# I2CSlave_OnBoard.net
KiCad netlist of a schematic drawn in EAGLE
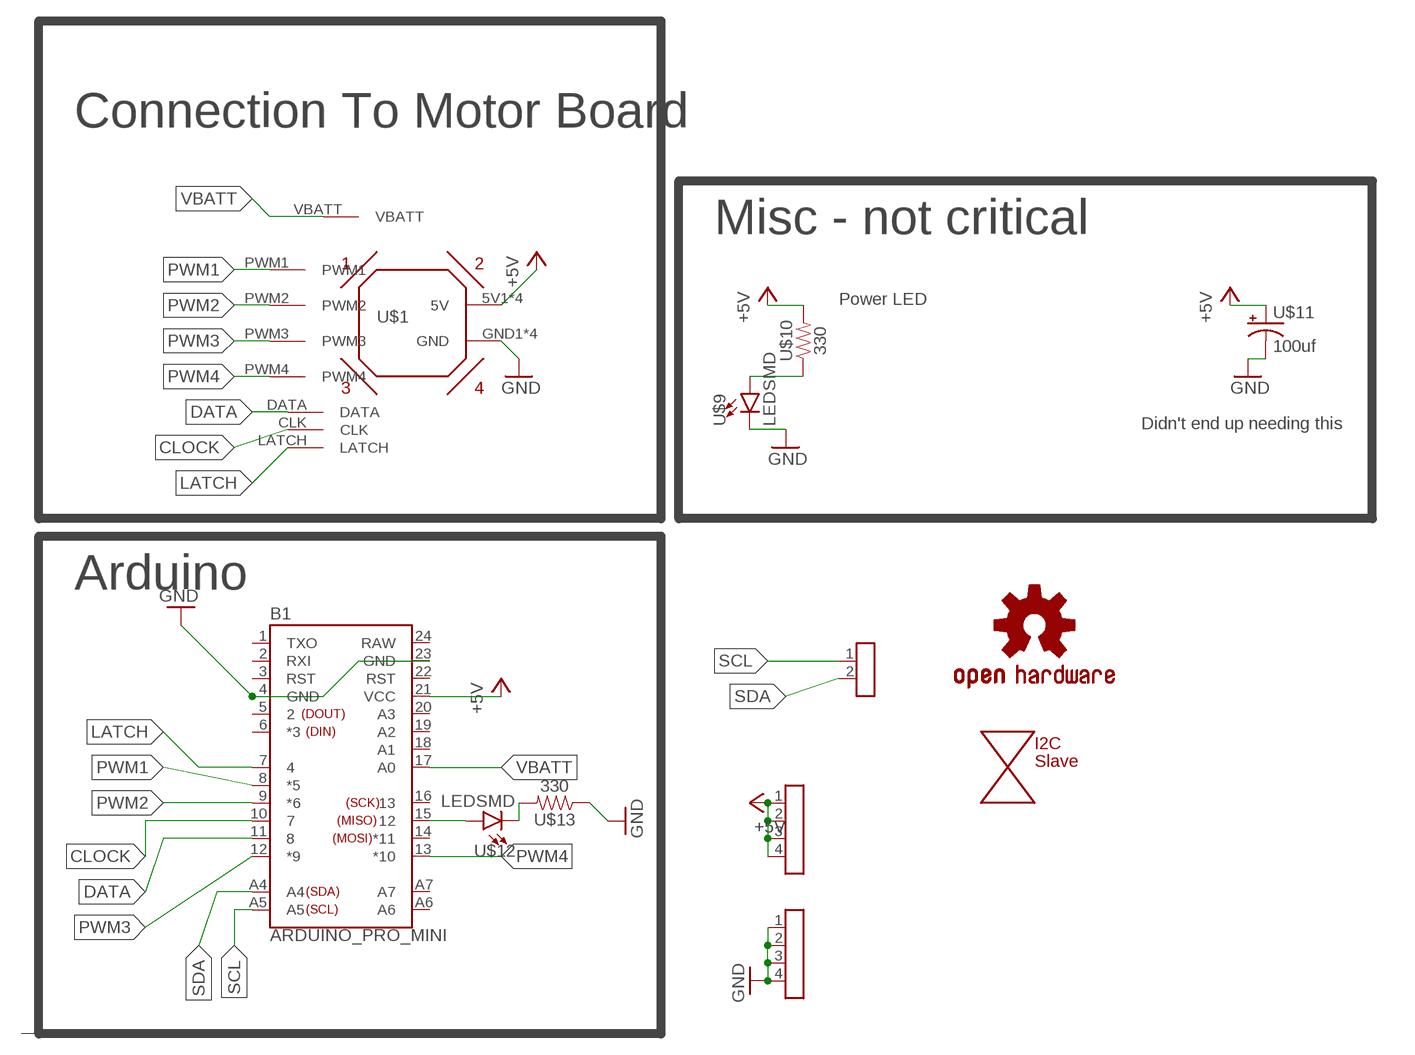
[diagram p0: schematic, sheet 1]

(export (version "E")
  (design (tool "Eeschema 10.0.6"))
  (components
    (comp (ref "B1")
      (value "ARDUINO_PRO_MINI")
      (footprint "eagle-import:ARDUINO_PRO_MINI")
      (libsource (lib "eagle-import") (part "ARDUINO_PRO_MINI"))
    )
    (comp (ref "I2C")
      (value "Slave")
      (footprint "eagle-import:ANNOTATION")
      (libsource (lib "eagle-import") (part "ANNOTATION"))
    )
    (comp (ref "LOGO1")
      (value "OSHW-LOGOM")
      (footprint "eagle-import:OSHW-LOGO-M")
      (libsource (lib "eagle-import") (part "OSHW-LOGOM"))
    )
    (comp (ref "U$1")
      (value "OMNIBOARD")
      (footprint "eagle-import:OMNIBOARD")
      (libsource (lib "eagle-import") (part "OMNIBOARD"))
    )
    (comp (ref "U$2")
      (value "2XHEADER")
      (footprint "eagle-import:2XHEADER")
      (libsource (lib "eagle-import") (part "2XHEADER"))
    )
    (comp (ref "U$3")
      (value "4XHEADER")
      (footprint "eagle-import:4XHEADER")
      (libsource (lib "eagle-import") (part "4XHEADER"))
    )
    (comp (ref "U$4")
      (value "4XHEADER")
      (footprint "eagle-import:4XHEADER")
      (libsource (lib "eagle-import") (part "4XHEADER"))
    )
    (comp (ref "U$9")
      (value "LEDSMD")
      (footprint "eagle-import:LED_SMD")
      (libsource (lib "eagle-import") (part "LEDSMD"))
    )
    (comp (ref "U$10")
      (value "330")
      (footprint "eagle-import:R1206")
      (libsource (lib "eagle-import") (part "RESISTORSMD"))
    )
    (comp (ref "U$11")
      (value "100uf")
      (footprint "eagle-import:CAP_E")
      (libsource (lib "eagle-import") (part "CAP_EMED"))
    )
    (comp (ref "U$12")
      (value "LEDSMD")
      (footprint "eagle-import:LED_SMD")
      (libsource (lib "eagle-import") (part "LEDSMD"))
    )
    (comp (ref "U$13")
      (value "330")
      (footprint "eagle-import:R1206")
      (libsource (lib "eagle-import") (part "RESISTORSMD"))
    )
  )
  (nets
    (net (code "1") (name "+5V") (class "Default")
      (node (ref "B1") (pin "21") (pinfunction "VCC_21") (pintype "power_in"))
      (node (ref "U$1") (pin "5V1") (pinfunction "5V_5V1") (pintype "passive"))
      (node (ref "U$1") (pin "5V2") (pinfunction "5V_5V2") (pintype "passive"))
      (node (ref "U$1") (pin "5V3") (pinfunction "5V_5V3") (pintype "passive"))
      (node (ref "U$1") (pin "5V4") (pinfunction "5V_5V4") (pintype "passive"))
      (node (ref "U$10") (pin "2") (pinfunction "2_2") (pintype "passive"))
      (node (ref "U$11") (pin "+") (pinfunction "+_+") (pintype "passive"))
      (node (ref "U$3") (pin "1") (pinfunction "1_1") (pintype "passive"))
      (node (ref "U$3") (pin "2") (pinfunction "2_2") (pintype "passive"))
      (node (ref "U$3") (pin "3") (pinfunction "3_3") (pintype "passive"))
      (node (ref "U$3") (pin "4") (pinfunction "4_4") (pintype "passive"))
    )
    (net (code "2") (name "/RAW") (class "Default")
      (node (ref "B1") (pin "24") (pinfunction "RAW_24") (pintype "power_in"))
    )
    (net (code "3") (name "CLOCK") (class "Default")
      (node (ref "B1") (pin "10") (pinfunction "7_10") (pintype "bidirectional"))
      (node (ref "U$1") (pin "CLK") (pinfunction "CLK_CLK") (pintype "passive"))
    )
    (net (code "4") (name "DATA") (class "Default")
      (node (ref "B1") (pin "11") (pinfunction "8_11") (pintype "bidirectional"))
      (node (ref "U$1") (pin "DATA") (pinfunction "DATA_DATA") (pintype "passive"))
    )
    (net (code "5") (name "GND") (class "Default")
      (node (ref "B1") (pin "23") (pinfunction "GND_23") (pintype "power_in"))
      (node (ref "B1") (pin "4") (pinfunction "GND_4") (pintype "power_in"))
      (node (ref "U$1") (pin "GND1") (pinfunction "GND_GND1") (pintype "passive"))
      (node (ref "U$1") (pin "GND2") (pinfunction "GND_GND2") (pintype "passive"))
      (node (ref "U$1") (pin "GND3") (pinfunction "GND_GND3") (pintype "passive"))
      (node (ref "U$1") (pin "GND4") (pinfunction "GND_GND4") (pintype "passive"))
      (node (ref "U$11") (pin "-") (pinfunction "-_-") (pintype "passive"))
      (node (ref "U$13") (pin "1") (pinfunction "1_1") (pintype "passive"))
      (node (ref "U$4") (pin "1") (pinfunction "1_1") (pintype "passive"))
      (node (ref "U$4") (pin "2") (pinfunction "2_2") (pintype "passive"))
      (node (ref "U$4") (pin "3") (pinfunction "3_3") (pintype "passive"))
      (node (ref "U$4") (pin "4") (pinfunction "4_4") (pintype "passive"))
      (node (ref "U$9") (pin "C") (pinfunction "C_C") (pintype "passive"))
    )
    (net (code "6") (name "LATCH") (class "Default")
      (node (ref "B1") (pin "7") (pinfunction "4_7") (pintype "bidirectional"))
      (node (ref "U$1") (pin "LATCH") (pinfunction "LATCH_LATCH") (pintype "passive"))
    )
    (net (code "7") (name "Net-(B1-12)") (class "Default")
      (node (ref "B1") (pin "15") (pinfunction "12_15") (pintype "bidirectional"))
      (node (ref "U$12") (pin "A") (pinfunction "A_A") (pintype "passive"))
    )
    (net (code "8") (name "Net-(U$10-Pad1)") (class "Default")
      (node (ref "U$10") (pin "1") (pinfunction "1_1") (pintype "passive"))
      (node (ref "U$9") (pin "A") (pinfunction "A_A") (pintype "passive"))
    )
    (net (code "9") (name "Net-(U$12-PadC)") (class "Default")
      (node (ref "U$12") (pin "C") (pinfunction "C_C") (pintype "passive"))
      (node (ref "U$13") (pin "2") (pinfunction "2_2") (pintype "passive"))
    )
    (net (code "10") (name "PWM1") (class "Default")
      (node (ref "B1") (pin "8") (pinfunction "*5_8") (pintype "bidirectional"))
      (node (ref "U$1") (pin "PWM1") (pinfunction "PWM1_PWM1") (pintype "passive"))
    )
    (net (code "11") (name "PWM2") (class "Default")
      (node (ref "B1") (pin "9") (pinfunction "*6_9") (pintype "bidirectional"))
      (node (ref "U$1") (pin "PWM2") (pinfunction "PWM2_PWM2") (pintype "passive"))
    )
    (net (code "12") (name "PWM3") (class "Default")
      (node (ref "B1") (pin "12") (pinfunction "*9_12") (pintype "bidirectional"))
      (node (ref "U$1") (pin "PWM3") (pinfunction "PWM3_PWM3") (pintype "passive"))
    )
    (net (code "13") (name "PWM4") (class "Default")
      (node (ref "B1") (pin "13") (pinfunction "*10_13") (pintype "bidirectional"))
      (node (ref "U$1") (pin "PWM4") (pinfunction "PWM4_PWM4") (pintype "passive"))
    )
    (net (code "14") (name "SCL") (class "Default")
      (node (ref "B1") (pin "A5") (pinfunction "A5_A5") (pintype "bidirectional"))
      (node (ref "U$2") (pin "1") (pinfunction "1_1") (pintype "passive"))
    )
    (net (code "15") (name "SDA") (class "Default")
      (node (ref "B1") (pin "A4") (pinfunction "A4_A4") (pintype "bidirectional"))
      (node (ref "U$2") (pin "2") (pinfunction "2_2") (pintype "passive"))
    )
    (net (code "16") (name "VBATT") (class "Default")
      (node (ref "B1") (pin "17") (pinfunction "A0_17") (pintype "bidirectional"))
      (node (ref "U$1") (pin "VBATT") (pinfunction "VBATT_VBATT") (pintype "passive"))
    )
    (net (code "17") (name "unconnected-(B1-*3-Pad6)") (class "Default")
      (node (ref "B1") (pin "6") (pinfunction "*3_6") (pintype "bidirectional"))
    )
    (net (code "18") (name "unconnected-(B1-*11-Pad14)") (class "Default")
      (node (ref "B1") (pin "14") (pinfunction "*11_14") (pintype "bidirectional"))
    )
    (net (code "19") (name "unconnected-(B1-2-Pad5)") (class "Default")
      (node (ref "B1") (pin "5") (pinfunction "2_5") (pintype "bidirectional"))
    )
    (net (code "20") (name "unconnected-(B1-13-Pad16)") (class "Default")
      (node (ref "B1") (pin "16") (pinfunction "13_16") (pintype "bidirectional"))
    )
    (net (code "21") (name "unconnected-(B1-A1-Pad18)") (class "Default")
      (node (ref "B1") (pin "18") (pinfunction "A1_18") (pintype "bidirectional"))
    )
    (net (code "22") (name "unconnected-(B1-A2-Pad19)") (class "Default")
      (node (ref "B1") (pin "19") (pinfunction "A2_19") (pintype "bidirectional"))
    )
    (net (code "23") (name "unconnected-(B1-A3-Pad20)") (class "Default")
      (node (ref "B1") (pin "20") (pinfunction "A3_20") (pintype "bidirectional"))
    )
    (net (code "24") (name "unconnected-(B1-PadA6)") (class "Default")
      (node (ref "B1") (pin "A6") (pinfunction "A6_A6") (pintype "bidirectional"))
    )
    (net (code "25") (name "unconnected-(B1-PadA7)") (class "Default")
      (node (ref "B1") (pin "A7") (pinfunction "A7_A7") (pintype "bidirectional"))
    )
    (net (code "26") (name "unconnected-(B1-RST-Pad3)") (class "Default")
      (node (ref "B1") (pin "3") (pinfunction "RST_3") (pintype "bidirectional"))
    )
    (net (code "27") (name "unconnected-(B1-RST-Pad22)") (class "Default")
      (node (ref "B1") (pin "22") (pinfunction "RST_22") (pintype "bidirectional"))
    )
    (net (code "28") (name "unconnected-(B1-RXI-Pad2)") (class "Default")
      (node (ref "B1") (pin "2") (pinfunction "RXI_2") (pintype "bidirectional"))
    )
    (net (code "29") (name "unconnected-(B1-TXO-Pad1)") (class "Default")
      (node (ref "B1") (pin "1") (pinfunction "TXO_1") (pintype "bidirectional"))
    )
  )
)
